# BEP33_2panel_v2_90Gradtvm802.net
KiCad netlist of a schematic drawn in EAGLE
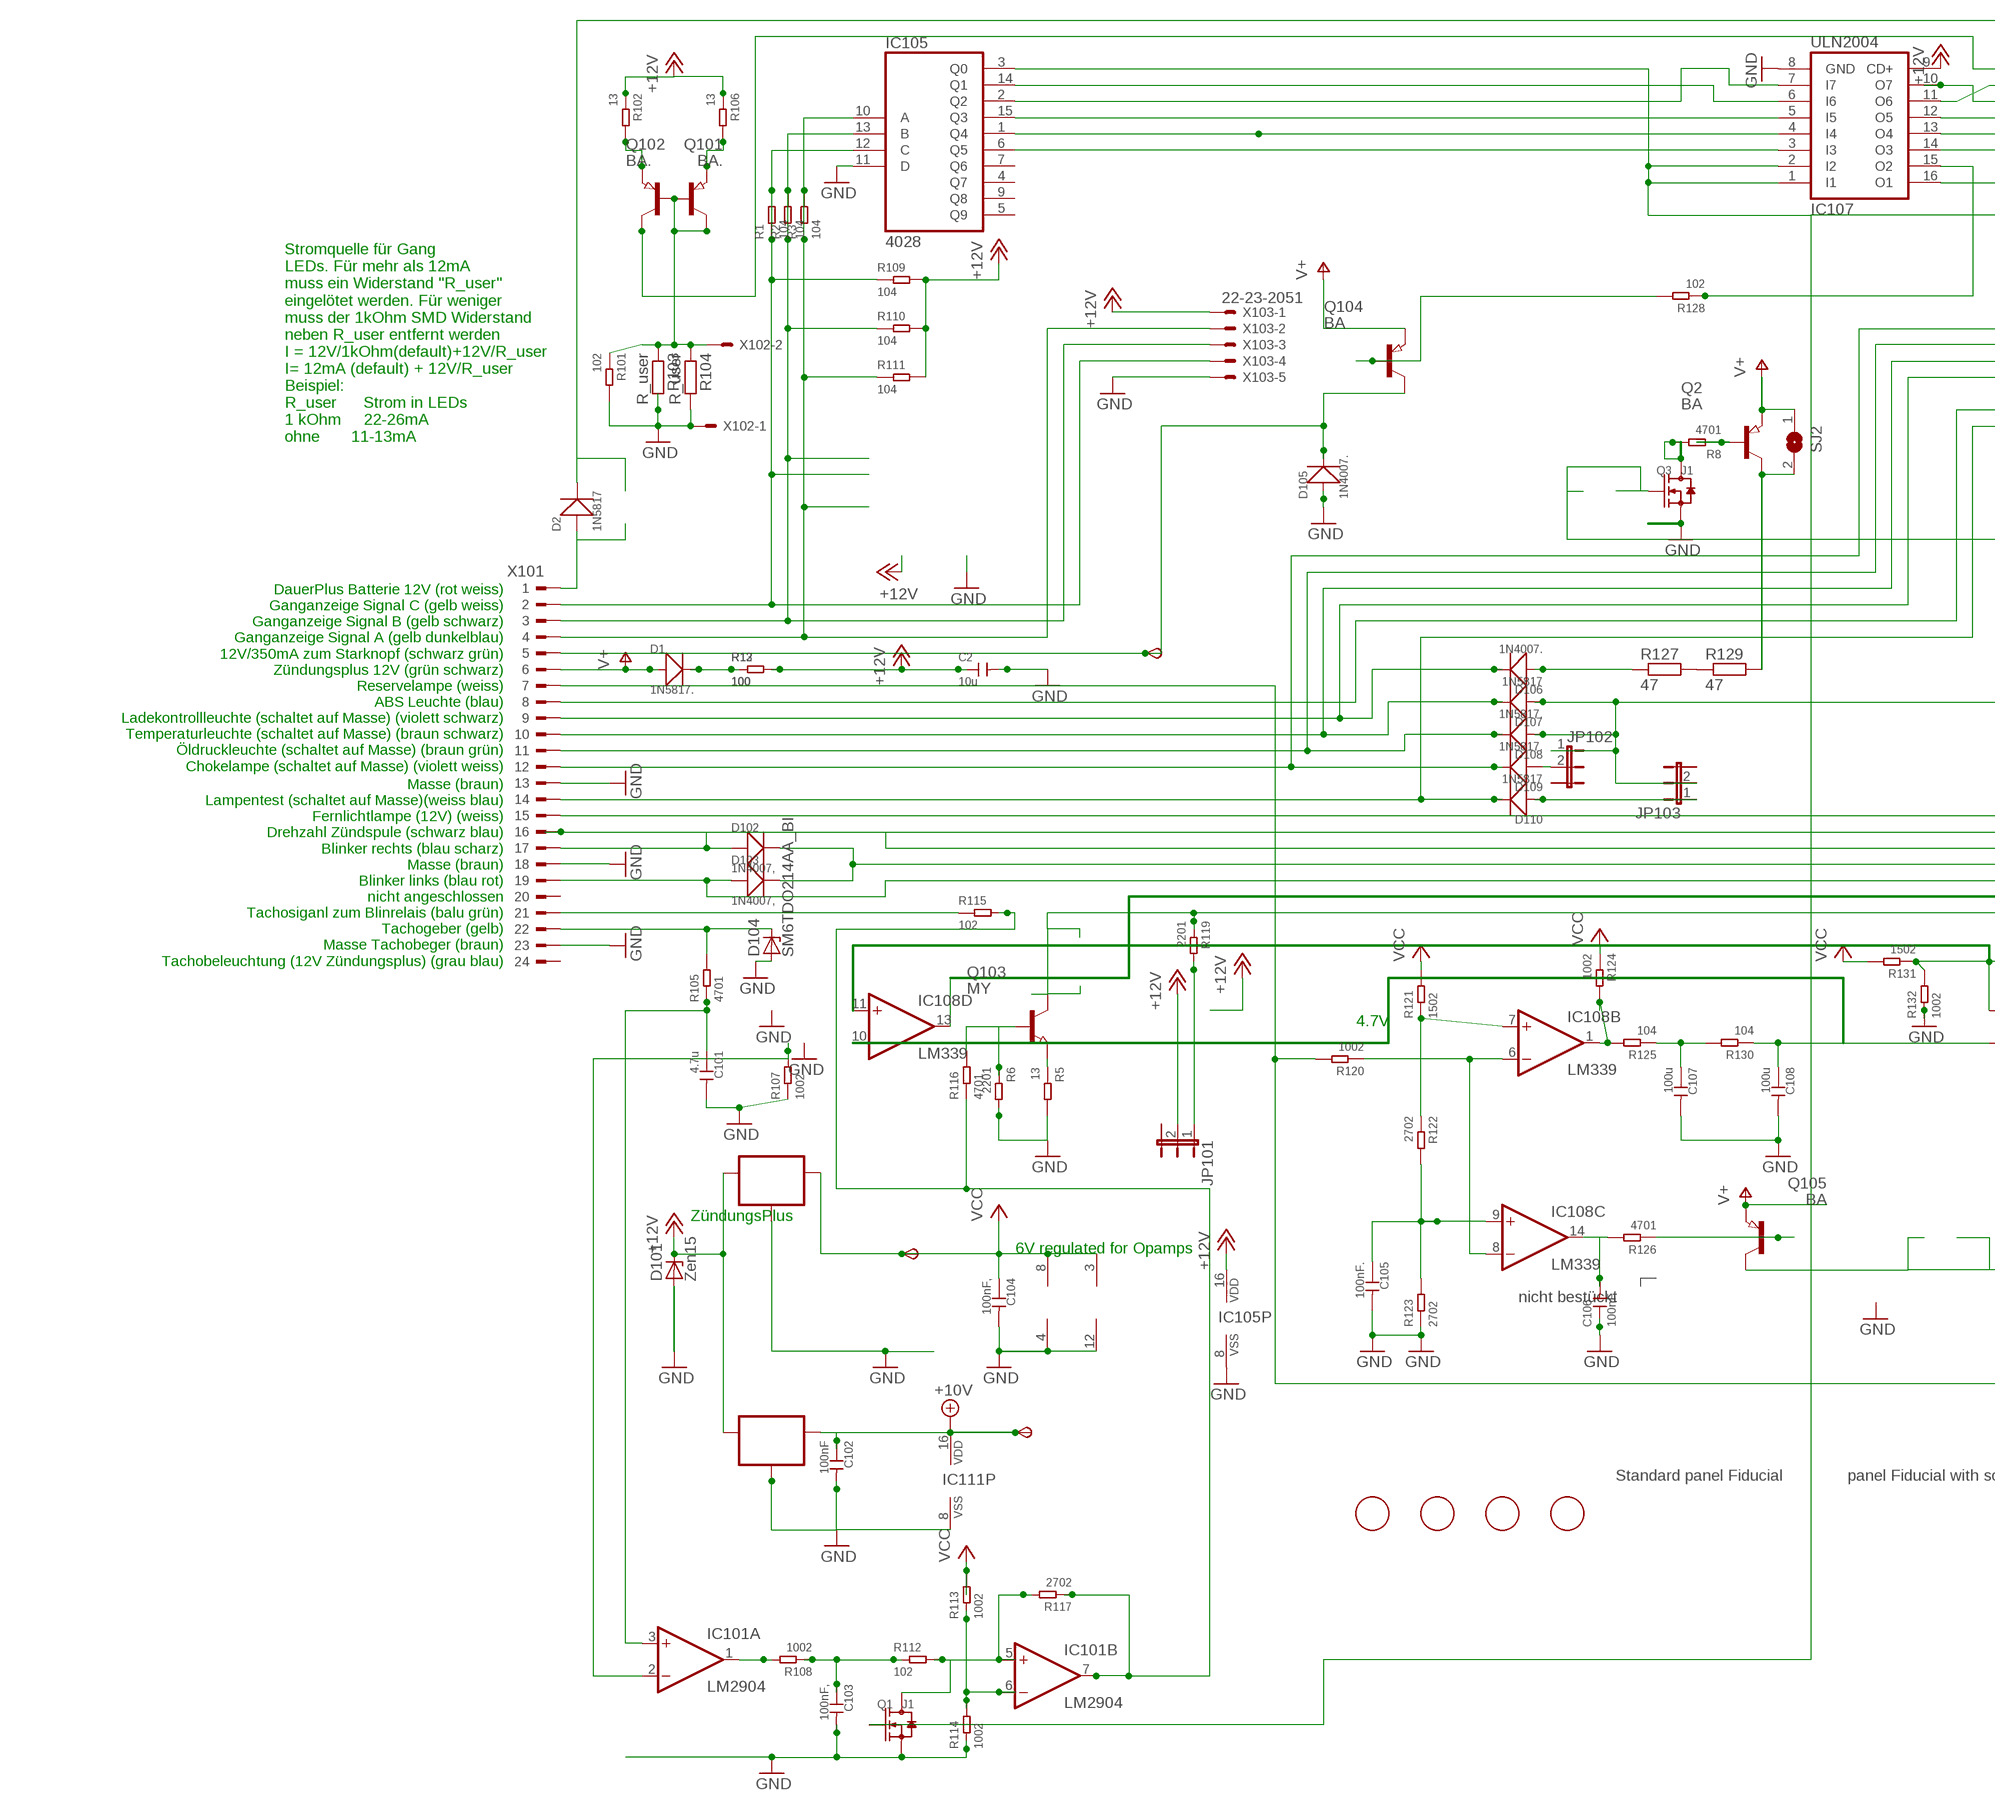
[diagram p0: schematic, sheet 1, part 1 of 2]
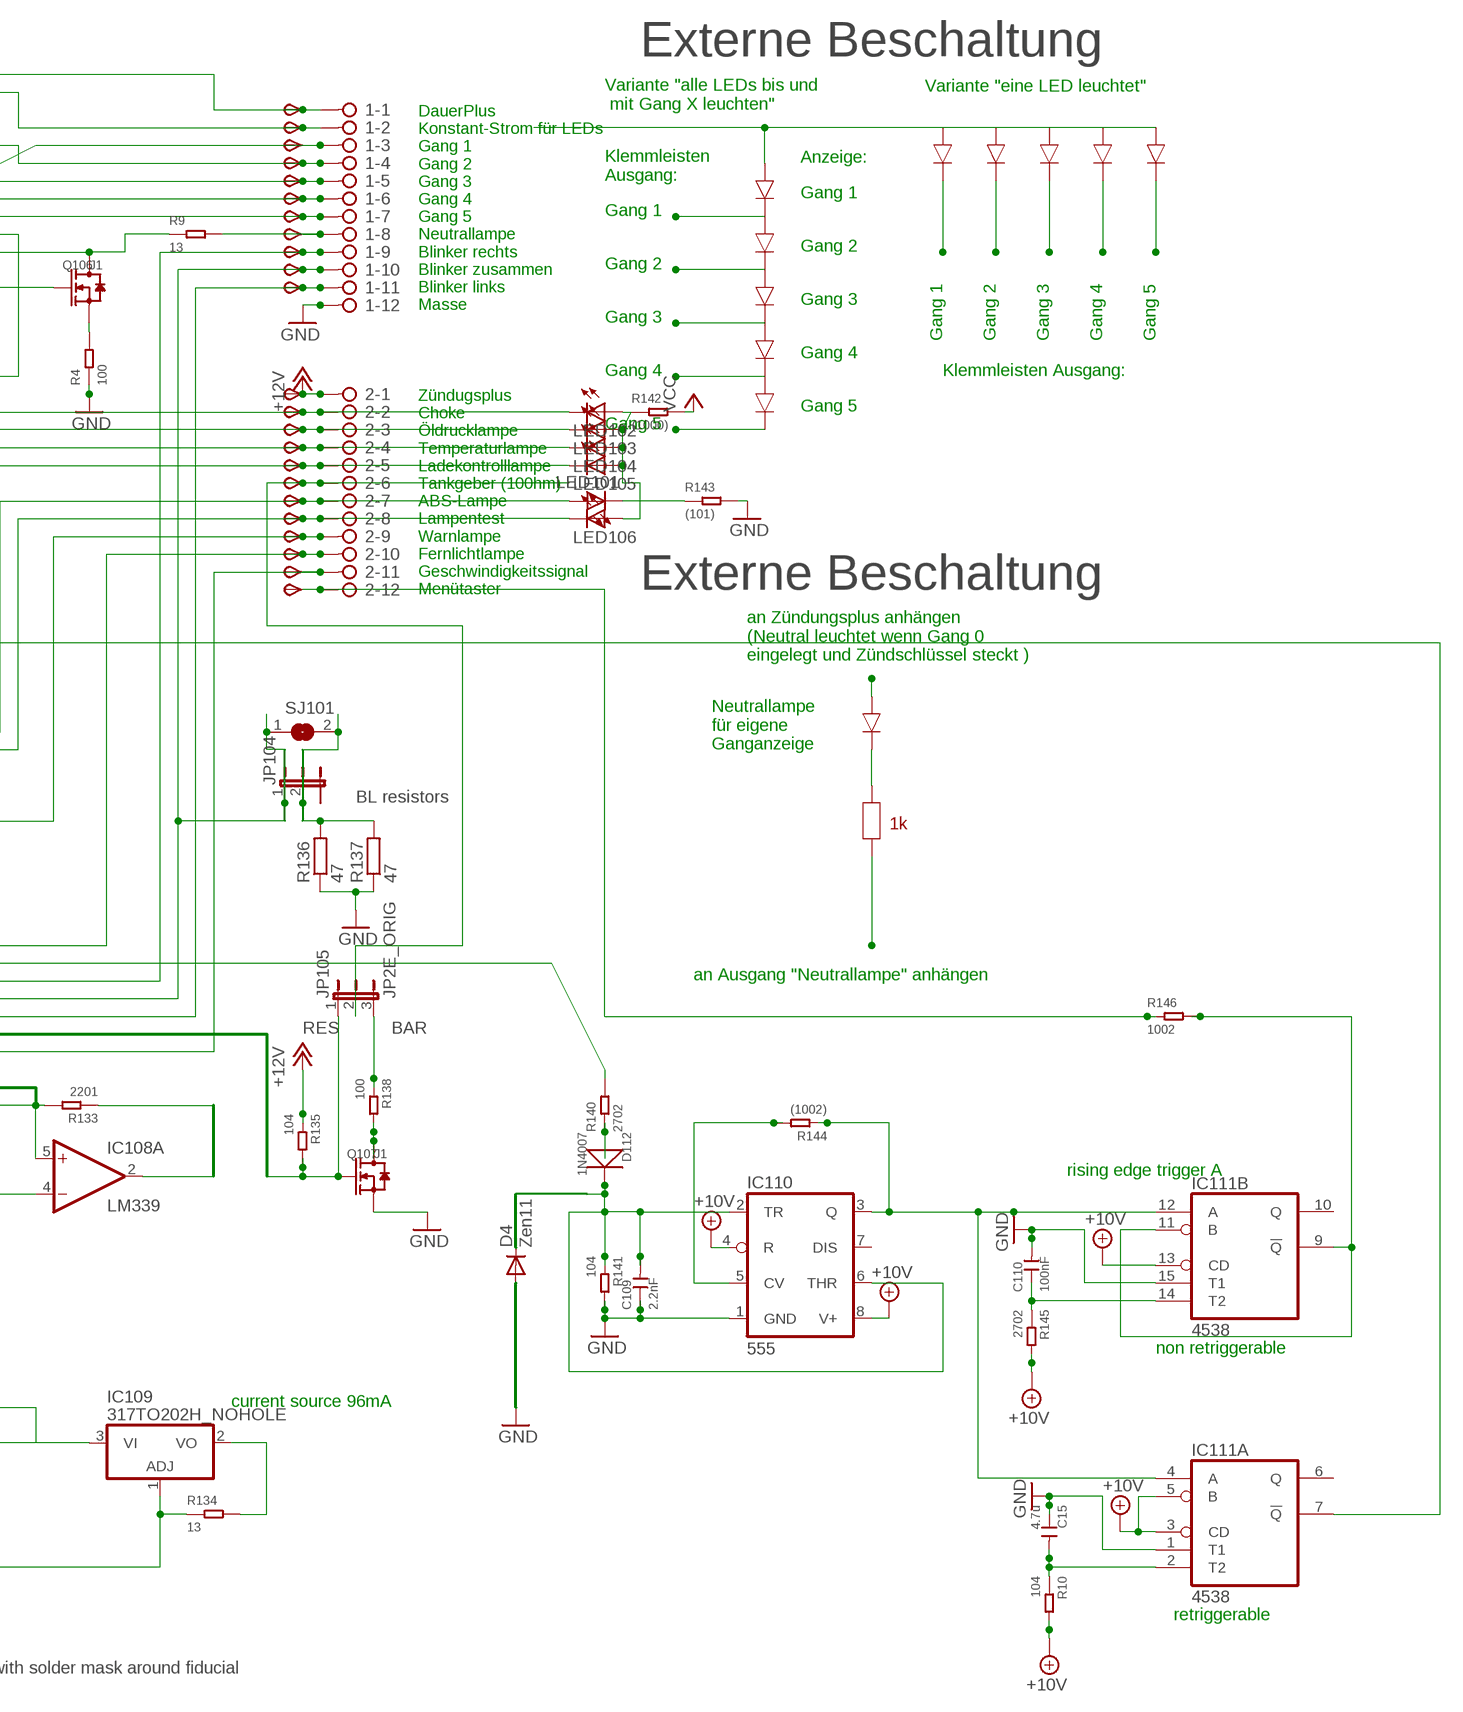
[diagram p1: schematic, sheet 1, part 2 of 2]

(export (version "E")
  (design (tool "Eeschema 10.0.6"))
  (components
    (comp (ref "1")
      (value "2081-1132")
      (footprint "eagle-import:12-PIN")
      (libsource (lib "eagle-import") (part "2081-1132"))
    )
    (comp (ref "2")
      (value "2081-1132")
      (footprint "eagle-import:12-PIN")
      (libsource (lib "eagle-import") (part "2081-1132"))
    )
    (comp (ref "6V")
      (value "TPSB2.0")
      (footprint "eagle-import:B2.0")
      (libsource (lib "eagle-import") (part "TPSB2.0"))
    )
    (comp (ref "10V")
      (value "TPSB2.0")
      (footprint "eagle-import:B2.0")
      (libsource (lib "eagle-import") (part "TPSB2.0"))
    )
    (comp (ref "C2")
      (value "10u")
      (footprint "eagle-import:C1206")
      (fields (field (name "MPN") "GRM31CR60J107ME39L"))
      (libsource (lib "eagle-import") (part "CERAMIC-100UF-6.3V-20%-X5R(1206)"))
    )
    (comp (ref "C15")
      (value "4.7u")
      (footprint "eagle-import:C0805")
      (fields (field (name "MPN") "CC0805KKX5R8BB475"))
      (libsource (lib "eagle-import") (part "CERAMIC-4.7UF-25V-10%-X5R(0805)"))
    )
    (comp (ref "C101")
      (value "4.7u")
      (footprint "eagle-import:C0805")
      (fields (field (name "MPN") "CC0805KKX5R8BB475"))
      (libsource (lib "eagle-import") (part "CERAMIC-4.7UF-25V-10%-X5R(0805)"))
    )
    (comp (ref "C102")
      (value "100nF")
      (footprint "eagle-import:C0805")
      (fields (field (name "MPN") "CC0805KRX7R9BB104"))
      (libsource (lib "eagle-import") (part "CERAMIC-100NF-50V-10%-X7R(0805)"))
    )
    (comp (ref "C103")
      (value "100nF,")
      (footprint "eagle-import:C0805")
      (fields (field (name "MPN") "CC0805KRX7R9BB104"))
      (libsource (lib "eagle-import") (part "CERAMIC-100NF-50V-10%-X7R(0805)"))
    )
    (comp (ref "C104")
      (value "100nF,")
      (footprint "eagle-import:C0805")
      (fields (field (name "MPN") "CC0805KRX7R9BB104"))
      (libsource (lib "eagle-import") (part "CERAMIC-100NF-50V-10%-X7R(0805)"))
    )
    (comp (ref "C105")
      (value "100nF.")
      (footprint "eagle-import:C0805")
      (fields (field (name "MPN") "CC0805KRX7R9BB104"))
      (libsource (lib "eagle-import") (part "CERAMIC-100NF-50V-10%-X7R(0805)"))
    )
    (comp (ref "C106")
      (value "100nF.")
      (footprint "eagle-import:C0805")
      (fields (field (name "MPN") "CC0805KRX7R9BB104"))
      (libsource (lib "eagle-import") (part "CERAMIC-100NF-50V-10%-X7R(0805)"))
    )
    (comp (ref "C107")
      (value "100u")
      (footprint "eagle-import:C1206")
      (fields (field (name "MPN") "GRM31CR60J107ME39L"))
      (libsource (lib "eagle-import") (part "CERAMIC-100UF-6.3V-20%-X5R(1206)"))
    )
    (comp (ref "C108")
      (value "100u")
      (footprint "eagle-import:C1206")
      (fields (field (name "MPN") "GRM31CR60J107ME39L"))
      (libsource (lib "eagle-import") (part "CERAMIC-100UF-6.3V-20%-X5R(1206)"))
    )
    (comp (ref "C109")
      (value "2.2nF")
      (footprint "eagle-import:C0805")
      (fields (field (name "MPN") "CC0805KRX7R9BB104"))
      (libsource (lib "eagle-import") (part "CERAMIC-100NF-50V-10%-X7R(0805)"))
    )
    (comp (ref "C110")
      (value "100nF")
      (footprint "eagle-import:C0805")
      (fields (field (name "MPN") "CC0805KRX7R9BB104"))
      (libsource (lib "eagle-import") (part "CERAMIC-100NF-50V-10%-X7R(0805)"))
    )
    (comp (ref "D1")
      (value "1N5817.")
      (footprint "eagle-import:DO-214AC_SLIM")
      (libsource (lib "eagle-import") (part "DIODE-GEN-PURPOSE-1KV-1A(DO-214AC)DO-214AC/1206"))
    )
    (comp (ref "D2")
      (value "1N5817")
      (footprint "eagle-import:DO-214AC_SLIM")
      (libsource (lib "eagle-import") (part "DIODE-GEN-PURPOSE-1KV-1A(DO-214AC)DO-214AC/1206"))
    )
    (comp (ref "D4")
      (value "Zen11")
      (footprint "eagle-import:SOD-123_MINI-SMA")
      (libsource (lib "eagle-import") (part "CGRM400-G1"))
    )
    (comp (ref "D101")
      (value "Zen15")
      (footprint "eagle-import:DO214AA")
      (libsource (lib "eagle-import") (part "SM6T"))
    )
    (comp (ref "D102")
      (value "1N4007,")
      (footprint "eagle-import:DO-214AC")
      (fields (field (name "MPN") "1N4007"))
      (libsource (lib "eagle-import") (part "DIODE-GEN-PURPOSE-1KV-1A(DO-214AC)"))
    )
    (comp (ref "D103")
      (value "1N4007,")
      (footprint "eagle-import:DO-214AC")
      (fields (field (name "MPN") "1N4007"))
      (libsource (lib "eagle-import") (part "DIODE-GEN-PURPOSE-1KV-1A(DO-214AC)"))
    )
    (comp (ref "D104")
      (value "SM6TDO214AA_BI")
      (footprint "eagle-import:DO214AA_BI")
      (libsource (lib "eagle-import") (part "SM6TDO214AA_BI"))
    )
    (comp (ref "D105")
      (value "1N4007.")
      (footprint "eagle-import:DO-214AC")
      (fields (field (name "MPN") "1N4007"))
      (libsource (lib "eagle-import") (part "DIODE-GEN-PURPOSE-1KV-1A(DO-214AC)"))
    )
    (comp (ref "D106")
      (value "1N4007.")
      (footprint "eagle-import:DO-214AC")
      (fields (field (name "MPN") "1N4007"))
      (libsource (lib "eagle-import") (part "DIODE-GEN-PURPOSE-1KV-1A(DO-214AC)"))
    )
    (comp (ref "D107")
      (value "1N5817")
      (footprint "eagle-import:DO-214AC_SLIM")
      (libsource (lib "eagle-import") (part "DIODE-GEN-PURPOSE-1KV-1A(DO-214AC)DO-214AC/1206"))
    )
    (comp (ref "D108")
      (value "1N5817.")
      (footprint "eagle-import:DO-214AC_SLIM")
      (libsource (lib "eagle-import") (part "DIODE-GEN-PURPOSE-1KV-1A(DO-214AC)DO-214AC/1206"))
    )
    (comp (ref "D109")
      (value "1N5817.")
      (footprint "eagle-import:DO-214AC_SLIM")
      (libsource (lib "eagle-import") (part "DIODE-GEN-PURPOSE-1KV-1A(DO-214AC)DO-214AC/1206"))
    )
    (comp (ref "D110")
      (value "1N5817")
      (footprint "eagle-import:DO-214AC_SLIM")
      (libsource (lib "eagle-import") (part "DIODE-GEN-PURPOSE-1KV-1A(DO-214AC)DO-214AC/1206"))
    )
    (comp (ref "D112")
      (value "1N4007")
      (footprint "eagle-import:DO-214AC")
      (libsource (lib "eagle-import") (part "DIODE-GEN-PURPOSE-1KV-1A(DO-214AC)"))
    )
    (comp (ref "FID1")
      (value "FIDUCIAL")
      (footprint "eagle-import:FIDUCIAL_1MM")
      (libsource (lib "eagle-import") (part "FIDUCIAL"))
    )
    (comp (ref "FID2")
      (value "FIDUCIAL")
      (footprint "eagle-import:FIDUCIAL_1MM")
      (libsource (lib "eagle-import") (part "FIDUCIAL"))
    )
    (comp (ref "FID102")
      (value "FIDUCIAL")
      (footprint "eagle-import:FIDUCIAL_1MM")
      (libsource (lib "eagle-import") (part "FIDUCIAL"))
    )
    (comp (ref "FID104")
      (value "FIDUCIAL")
      (footprint "eagle-import:FIDUCIAL_1MM")
      (libsource (lib "eagle-import") (part "FIDUCIAL"))
    )
    (comp (ref "IC101")
      (value "LM2904")
      (footprint "eagle-import:SO08")
      (libsource (lib "eagle-import") (part "LM358D"))
    )
    (comp (ref "IC102")
      (value "78L06")
      (footprint "eagle-import:SOT89_ROUND")
      (libsource (lib "eagle-import") (part "78LXXSOT89_ROUND"))
    )
    (comp (ref "IC104")
      (value "78L10")
      (footprint "eagle-import:SOT89_ROUND")
      (libsource (lib "eagle-import") (part "78LXXSOT89_ROUND"))
    )
    (comp (ref "IC105")
      (value "4028")
      (footprint "eagle-import:SO16")
      (libsource (lib "eagle-import") (part "4028D"))
    )
    (comp (ref "IC107")
      (value "ULN2004")
      (footprint "eagle-import:SO16")
      (libsource (lib "eagle-import") (part "ULN2004AD"))
    )
    (comp (ref "IC108")
      (value "LM339")
      (footprint "eagle-import:SO14")
      (libsource (lib "eagle-import") (part "LM339D"))
    )
    (comp (ref "IC109")
      (value "317TO202H_NOHOLE")
      (footprint "eagle-import:TO220H_NOHOLE")
      (libsource (lib "eagle-import") (part "317TO202H_NOHOLE"))
    )
    (comp (ref "IC110")
      (value "555")
      (footprint "eagle-import:SO08")
      (libsource (lib "eagle-import") (part "555DNE"))
    )
    (comp (ref "IC111")
      (value "4538")
      (footprint "eagle-import:SO16")
      (libsource (lib "eagle-import") (part "4538D"))
    )
    (comp (ref "JP101")
      (value "JP2EJP2_SMALLPADS")
      (footprint "eagle-import:JP2_SMALLPADS")
      (libsource (lib "eagle-import") (part "JP2EJP2_SMALLPADS"))
    )
    (comp (ref "JP102")
      (value "JP2EJP2_SMALLPADS")
      (footprint "eagle-import:JP2_SMALLPADS")
      (libsource (lib "eagle-import") (part "JP2EJP2_SMALLPADS"))
    )
    (comp (ref "JP103")
      (value "JP2EJP2_SMALLPADS")
      (footprint "eagle-import:JP2_SMALLPADS")
      (libsource (lib "eagle-import") (part "JP2EJP2_SMALLPADS"))
    )
    (comp (ref "JP104")
      (value "JP2EJP2_SMALLPADS")
      (footprint "eagle-import:JP2_SMALLPADS")
      (libsource (lib "eagle-import") (part "JP2EJP2_SMALLPADS"))
    )
    (comp (ref "JP105")
      (value "JP2E_ORIG")
      (footprint "eagle-import:JP2_ORIG_SMALLPADS")
      (libsource (lib "eagle-import") (part "JP2E_ORIG"))
    )
    (comp (ref "LED101")
      (value "LEDLD260")
      (footprint "eagle-import:LD260")
      (libsource (lib "eagle-import") (part "LEDLD260"))
    )
    (comp (ref "LED102")
      (value "LEDLD260")
      (footprint "eagle-import:LD260")
      (libsource (lib "eagle-import") (part "LEDLD260"))
    )
    (comp (ref "LED103")
      (value "LEDLD260")
      (footprint "eagle-import:LD260")
      (libsource (lib "eagle-import") (part "LEDLD260"))
    )
    (comp (ref "LED104")
      (value "LEDLD260")
      (footprint "eagle-import:LD260")
      (libsource (lib "eagle-import") (part "LEDLD260"))
    )
    (comp (ref "LED105")
      (value "LEDLD260")
      (footprint "eagle-import:LD260")
      (libsource (lib "eagle-import") (part "LEDLD260"))
    )
    (comp (ref "LED106")
      (value "LEDLD260")
      (footprint "eagle-import:LD260")
      (libsource (lib "eagle-import") (part "LEDLD260"))
    )
    (comp (ref "Q1")
      (value "J1")
      (footprint "eagle-import:SOT-23")
      (fields (field (name "MPN") "BSS138W-7-F"))
      (libsource (lib "eagle-import") (part "SMD-MOSFET-N-CH-50V-200MA-BSS138W-7-F(SOT-23)"))
    )
    (comp (ref "Q2")
      (value "BA")
      (footprint "eagle-import:SOT89")
      (libsource (lib "eagle-import") (part "PNP-TRANSISTOR_SOT89"))
    )
    (comp (ref "Q3")
      (value "J1")
      (footprint "eagle-import:SOT-23")
      (fields (field (name "MPN") "BSS138W-7-F"))
      (libsource (lib "eagle-import") (part "SMD-MOSFET-N-CH-50V-200MA-BSS138W-7-F(SOT-23)"))
    )
    (comp (ref "Q101")
      (value "BA.")
      (footprint "eagle-import:SOT89")
      (libsource (lib "eagle-import") (part "PNP-TRANSISTOR_SOT89"))
    )
    (comp (ref "Q102")
      (value "BA.")
      (footprint "eagle-import:SOT89")
      (libsource (lib "eagle-import") (part "PNP-TRANSISTOR_SOT89"))
    )
    (comp (ref "Q103")
      (value "MY")
      (footprint "eagle-import:SOT89")
      (libsource (lib "eagle-import") (part "NPN-TRANSISTOR_SOT89"))
    )
    (comp (ref "Q104")
      (value "BA")
      (footprint "eagle-import:SOT89")
      (libsource (lib "eagle-import") (part "PNP-TRANSISTOR_SOT89"))
    )
    (comp (ref "Q105")
      (value "BA")
      (footprint "eagle-import:SOT89")
      (libsource (lib "eagle-import") (part "PNP-TRANSISTOR_SOT89"))
    )
    (comp (ref "Q106")
      (value "J1")
      (footprint "eagle-import:SOT-23")
      (fields (field (name "MPN") "BSS138W-7-F"))
      (libsource (lib "eagle-import") (part "SMD-MOSFET-N-CH-50V-200MA-BSS138W-7-F(SOT-23)"))
    )
    (comp (ref "Q107")
      (value "J1")
      (footprint "eagle-import:SOT-23")
      (fields (field (name "MPN") "BSS138W-7-F"))
      (libsource (lib "eagle-import") (part "SMD-MOSFET-N-CH-50V-200MA-BSS138W-7-F(SOT-23)"))
    )
    (comp (ref "R1")
      (value "104")
      (footprint "eagle-import:R0805")
      (fields (field (name "MPN") "RC0805FR-0710KL"))
      (libsource (lib "eagle-import") (part "SMD-RES-10K-1%-1/8W(0805)"))
    )
    (comp (ref "R2")
      (value "104")
      (footprint "eagle-import:R0805")
      (fields (field (name "MPN") "RC0805FR-0710KL"))
      (libsource (lib "eagle-import") (part "SMD-RES-10K-1%-1/8W(0805)"))
    )
    (comp (ref "R3")
      (value "104")
      (footprint "eagle-import:R0805")
      (fields (field (name "MPN") "RC0805FR-0710KL"))
      (libsource (lib "eagle-import") (part "SMD-RES-10K-1%-1/8W(0805)"))
    )
    (comp (ref "R4")
      (value "100")
      (footprint "eagle-import:R0805")
      (fields (field (name "MPN") "RC0805JR-07220RL"))
      (libsource (lib "eagle-import") (part "SMD-RES-220R-5%-1/8W(0805)"))
    )
    (comp (ref "R5")
      (value "13")
      (footprint "eagle-import:R1206")
      (fields (field (name "MPN") "RC1206JR-0713RL"))
      (libsource (lib "eagle-import") (part "SMD-RES-13R-5%-1/4W(1206)"))
    )
    (comp (ref "R6")
      (value "2201")
      (footprint "eagle-import:R0805")
      (fields (field (name "MPN") "RC0805JR-071KL"))
      (libsource (lib "eagle-import") (part "SMD-RES-1K-5%-1/8W(0805)"))
    )
    (comp (ref "R8")
      (value "4701")
      (footprint "eagle-import:R0805")
      (fields (field (name "MPN") "RC0805JR-074K7L"))
      (libsource (lib "eagle-import") (part "SMD-RES-4.7K-5%-1/8W(0805)"))
    )
    (comp (ref "R9")
      (value "13")
      (footprint "eagle-import:R1206")
      (fields (field (name "MPN") "RC1206JR-0713RL"))
      (libsource (lib "eagle-import") (part "SMD-RES-13R-5%-1/4W(1206)"))
    )
    (comp (ref "R10")
      (value "104")
      (footprint "eagle-import:R0805")
      (fields (field (name "MPN") "RC0805JR-074K7L"))
      (libsource (lib "eagle-import") (part "SMD-RES-4.7K-5%-1/8W(0805)"))
    )
    (comp (ref "R12")
      (value "100")
      (footprint "eagle-import:R0805")
      (fields (field (name "MPN") "RC0805JR-072K2L"))
      (libsource (lib "eagle-import") (part "SMD-RES-2.2K-5%-1/8W(0805)"))
    )
    (comp (ref "R13")
      (value "100")
      (footprint "eagle-import:R0805")
      (fields (field (name "MPN") "RC0805JR-072K2L"))
      (libsource (lib "eagle-import") (part "SMD-RES-2.2K-5%-1/8W(0805)"))
    )
    (comp (ref "R101")
      (value "102")
      (footprint "eagle-import:R0805")
      (fields (field (name "MPN") "RC0805JR-071KL"))
      (libsource (lib "eagle-import") (part "SMD-RES-1K-5%-1/8W(0805)"))
    )
    (comp (ref "R102")
      (value "13")
      (footprint "eagle-import:R1206")
      (fields (field (name "MPN") "RC1206JR-0713RL"))
      (libsource (lib "eagle-import") (part "SMD-RES-13R-5%-1/4W(1206)"))
    )
    (comp (ref "R103")
      (value "R_user")
      (footprint "eagle-import:R0805")
      (libsource (lib "eagle-import") (part "R-EU_R0805"))
    )
    (comp (ref "R104")
      (value "R_user")
      (footprint "eagle-import:R0805")
      (libsource (lib "eagle-import") (part "R-EU_R0805"))
    )
    (comp (ref "R105")
      (value "4701")
      (footprint "eagle-import:R0805")
      (fields (field (name "MPN") "RC0805JR-074K7L"))
      (libsource (lib "eagle-import") (part "SMD-RES-4.7K-5%-1/8W(0805)"))
    )
    (comp (ref "R106")
      (value "13")
      (footprint "eagle-import:R1206")
      (fields (field (name "MPN") "RC1206JR-0713RL"))
      (libsource (lib "eagle-import") (part "SMD-RES-13R-5%-1/4W(1206)"))
    )
    (comp (ref "R107")
      (value "1002")
      (footprint "eagle-import:R0805")
      (fields (field (name "MPN") "RC0805FR-0710KL"))
      (libsource (lib "eagle-import") (part "SMD-RES-10K-1%-1/8W(0805)"))
    )
    (comp (ref "R108")
      (value "1002")
      (footprint "eagle-import:R0805")
      (fields (field (name "MPN") "RC0805FR-0710KL"))
      (libsource (lib "eagle-import") (part "SMD-RES-10K-1%-1/8W(0805)"))
    )
    (comp (ref "R109")
      (value "104")
      (footprint "eagle-import:R0805")
      (fields (field (name "MPN") "RC0805FR-0710KL"))
      (libsource (lib "eagle-import") (part "SMD-RES-10K-1%-1/8W(0805)"))
    )
    (comp (ref "R110")
      (value "104")
      (footprint "eagle-import:R0805")
      (fields (field (name "MPN") "RC0805FR-0710KL"))
      (libsource (lib "eagle-import") (part "SMD-RES-10K-1%-1/8W(0805)"))
    )
    (comp (ref "R111")
      (value "104")
      (footprint "eagle-import:R0805")
      (fields (field (name "MPN") "RC0805FR-0710KL"))
      (libsource (lib "eagle-import") (part "SMD-RES-10K-1%-1/8W(0805)"))
    )
    (comp (ref "R112")
      (value "102")
      (footprint "eagle-import:R0805")
      (fields (field (name "MPN") "RC0805JR-071KL"))
      (libsource (lib "eagle-import") (part "SMD-RES-1K-5%-1/8W(0805)"))
    )
    (comp (ref "R113")
      (value "1002")
      (footprint "eagle-import:R0805")
      (fields (field (name "MPN") "RC0805JR-071KL"))
      (libsource (lib "eagle-import") (part "SMD-RES-1K-5%-1/8W(0805)"))
    )
    (comp (ref "R114")
      (value "1002")
      (footprint "eagle-import:R0805")
      (fields (field (name "MPN") "RC0805JR-071KL"))
      (libsource (lib "eagle-import") (part "SMD-RES-1K-5%-1/8W(0805)"))
    )
    (comp (ref "R115")
      (value "102")
      (footprint "eagle-import:R0805")
      (fields (field (name "MPN") "RC0805JR-07220RL"))
      (libsource (lib "eagle-import") (part "SMD-RES-220R-5%-1/8W(0805)"))
    )
    (comp (ref "R116")
      (value "4701")
      (footprint "eagle-import:R0805")
      (fields (field (name "MPN") "RC0805JR-074K7L"))
      (libsource (lib "eagle-import") (part "SMD-RES-4.7K-5%-1/8W(0805)"))
    )
    (comp (ref "R117")
      (value "2702")
      (footprint "eagle-import:R0805")
      (fields (field (name "MPN") "RC0805JR-074K7L"))
      (libsource (lib "eagle-import") (part "SMD-RES-4.7K-5%-1/8W(0805)"))
    )
    (comp (ref "R119")
      (value "2201")
      (footprint "eagle-import:R0805")
      (fields (field (name "MPN") "RC0805JR-072K2L"))
      (libsource (lib "eagle-import") (part "SMD-RES-2.2K-5%-1/8W(0805)"))
    )
    (comp (ref "R120")
      (value "1002")
      (footprint "eagle-import:R0805")
      (fields (field (name "MPN") "RC0805FR-0710KL"))
      (libsource (lib "eagle-import") (part "SMD-RES-10K-1%-1/8W(0805)"))
    )
    (comp (ref "R121")
      (value "1502")
      (footprint "eagle-import:R0805")
      (fields (field (name "MPN") "RC0805FR-0710KL"))
      (libsource (lib "eagle-import") (part "SMD-RES-10K-1%-1/8W(0805)"))
    )
    (comp (ref "R122")
      (value "2702")
      (footprint "eagle-import:R0805")
      (fields (field (name "MPN") "RC0805JR-074K7L"))
      (libsource (lib "eagle-import") (part "SMD-RES-4.7K-5%-1/8W(0805)"))
    )
    (comp (ref "R123")
      (value "2702")
      (footprint "eagle-import:R0805")
      (fields (field (name "MPN") "RC0805JR-074K7L"))
      (libsource (lib "eagle-import") (part "SMD-RES-4.7K-5%-1/8W(0805)"))
    )
    (comp (ref "R124")
      (value "1002")
      (footprint "eagle-import:R0805")
      (fields (field (name "MPN") "RC0805FR-0710KL"))
      (libsource (lib "eagle-import") (part "SMD-RES-10K-1%-1/8W(0805)"))
    )
    (comp (ref "R125")
      (value "104")
      (footprint "eagle-import:R0805")
      (fields (field (name "MPN") "RC0805FR-0710KL"))
      (libsource (lib "eagle-import") (part "SMD-RES-10K-1%-1/8W(0805)"))
    )
    (comp (ref "R126")
      (value "4701")
      (footprint "eagle-import:R0805")
      (fields (field (name "MPN") "RC0805JR-074K7L"))
      (libsource (lib "eagle-import") (part "SMD-RES-4.7K-5%-1/8W(0805)"))
    )
    (comp (ref "R127")
      (value "47")
      (footprint "eagle-import:V235_17_1MM")
      (libsource (lib "eagle-import") (part "R-EU_V235/17_1MM"))
    )
    (comp (ref "R128")
      (value "102")
      (footprint "eagle-import:R0805")
      (fields (field (name "MPN") "RC0805JR-071KL"))
      (libsource (lib "eagle-import") (part "SMD-RES-1K-5%-1/8W(0805)"))
    )
    (comp (ref "R129")
      (value "47")
      (footprint "eagle-import:V235_17_1MM")
      (libsource (lib "eagle-import") (part "R-EU_V235/17_1MM"))
    )
    (comp (ref "R130")
      (value "104")
      (footprint "eagle-import:R0805")
      (fields (field (name "MPN") "RC0805FR-0710KL"))
      (libsource (lib "eagle-import") (part "SMD-RES-10K-1%-1/8W(0805)"))
    )
    (comp (ref "R131")
      (value "1502")
      (footprint "eagle-import:R0805")
      (fields (field (name "MPN") "RC0805FR-0710KL"))
      (libsource (lib "eagle-import") (part "SMD-RES-10K-1%-1/8W(0805)"))
    )
    (comp (ref "R132")
      (value "1002")
      (footprint "eagle-import:R0805")
      (fields (field (name "MPN") "RC0805FR-0710KL"))
      (libsource (lib "eagle-import") (part "SMD-RES-10K-1%-1/8W(0805)"))
    )
    (comp (ref "R133")
      (value "2201")
      (footprint "eagle-import:R0805")
      (fields (field (name "MPN") "RC0805JR-072K2L"))
      (libsource (lib "eagle-import") (part "SMD-RES-2.2K-5%-1/8W(0805)"))
    )
    (comp (ref "R134")
      (value "13")
      (footprint "eagle-import:R1206")
      (fields (field (name "MPN") "RC1206JR-0713RL"))
      (libsource (lib "eagle-import") (part "SMD-RES-13R-5%-1/4W(1206)"))
    )
    (comp (ref "R135")
      (value "104")
      (footprint "eagle-import:R0805")
      (fields (field (name "MPN") "RC0805FR-0710KL"))
      (libsource (lib "eagle-import") (part "SMD-RES-10K-1%-1/8W(0805)"))
    )
    (comp (ref "R136")
      (value "47")
      (footprint "eagle-import:V235_17_1MM")
      (libsource (lib "eagle-import") (part "R-EU_V235/17_1MM"))
    )
    (comp (ref "R137")
      (value "47")
      (footprint "eagle-import:V235_17_1MM")
      (libsource (lib "eagle-import") (part "R-EU_V235/17_1MM"))
    )
    (comp (ref "R138")
      (value "100")
      (footprint "eagle-import:R0805")
      (fields (field (name "MPN") "RC0805JR-072K2L"))
      (libsource (lib "eagle-import") (part "SMD-RES-2.2K-5%-1/8W(0805)"))
    )
    (comp (ref "R140")
      (value "2702")
      (footprint "eagle-import:R0805")
      (fields (field (name "MPN") "RC0805FR-0710KL"))
      (libsource (lib "eagle-import") (part "SMD-RES-10K-1%-1/8W(0805)"))
    )
    (comp (ref "R141")
      (value "104")
      (footprint "eagle-import:R0805")
      (fields (field (name "MPN") "RC0805FR-0710KL"))
      (libsource (lib "eagle-import") (part "SMD-RES-10K-1%-1/8W(0805)"))
    )
    (comp (ref "R142")
      (value "(1000)")
      (footprint "eagle-import:R0805")
      (fields (field (name "MPN") "RC0805JR-07100RL"))
      (libsource (lib "eagle-import") (part "SMD-RES-100R-5%-1/8W(0805)"))
    )
    (comp (ref "R143")
      (value "(101)")
      (footprint "eagle-import:R0805")
      (fields (field (name "MPN") "RC0805JR-07100RL"))
      (libsource (lib "eagle-import") (part "SMD-RES-100R-5%-1/8W(0805)"))
    )
    (comp (ref "R144")
      (value "(1002)")
      (footprint "eagle-import:R0805")
      (fields (field (name "MPN") "RC0805FR-0710KL"))
      (libsource (lib "eagle-import") (part "SMD-RES-10K-1%-1/8W(0805)"))
    )
    (comp (ref "R145")
      (value "2702")
      (footprint "eagle-import:R0805")
      (fields (field (name "MPN") "RC0805JR-074K7L"))
      (libsource (lib "eagle-import") (part "SMD-RES-4.7K-5%-1/8W(0805)"))
    )
    (comp (ref "R146")
      (value "1002")
      (footprint "eagle-import:R0805")
      (fields (field (name "MPN") "RC0805JR-074K7L"))
      (libsource (lib "eagle-import") (part "SMD-RES-4.7K-5%-1/8W(0805)"))
    )
    (comp (ref "SJ2") (value "SJ") (footprint "eagle-import:SJ") (libsource (lib "eagle-import") (part "SJ")))
    (comp (ref "SJ101")
      (value "SJ")
      (footprint "eagle-import:SJ")
      (libsource (lib "eagle-import") (part "solder-jumper_SJ"))
    )
    (comp (ref "START")
      (value "TPSB2.0")
      (footprint "eagle-import:B2.0")
      (libsource (lib "eagle-import") (part "TPSB2.0"))
    )
    (comp (ref "TP1")
      (value "TPSB2.0")
      (footprint "eagle-import:B2.0")
      (libsource (lib "eagle-import") (part "TPSB2.0"))
    )
    (comp (ref "TP2")
      (value "TPSB2.0")
      (footprint "eagle-import:B2.0")
      (libsource (lib "eagle-import") (part "TPSB2.0"))
    )
    (comp (ref "TP3")
      (value "TPSB2.0")
      (footprint "eagle-import:B2.0")
      (libsource (lib "eagle-import") (part "TPSB2.0"))
    )
    (comp (ref "TP4")
      (value "TPSB2.0")
      (footprint "eagle-import:B2.0")
      (libsource (lib "eagle-import") (part "TPSB2.0"))
    )
    (comp (ref "TP5")
      (value "TPSB2.0")
      (footprint "eagle-import:B2.0")
      (libsource (lib "eagle-import") (part "TPSB2.0"))
    )
    (comp (ref "TP6")
      (value "TPSB2.0")
      (footprint "eagle-import:B2.0")
      (libsource (lib "eagle-import") (part "TPSB2.0"))
    )
    (comp (ref "TP7")
      (value "TPSB2.0")
      (footprint "eagle-import:B2.0")
      (libsource (lib "eagle-import") (part "TPSB2.0"))
    )
    (comp (ref "TP8")
      (value "TPSB2.0")
      (footprint "eagle-import:B2.0")
      (libsource (lib "eagle-import") (part "TPSB2.0"))
    )
    (comp (ref "TP9")
      (value "TPSB2.0")
      (footprint "eagle-import:B2.0")
      (libsource (lib "eagle-import") (part "TPSB2.0"))
    )
    (comp (ref "TP10")
      (value "TPSB2.0")
      (footprint "eagle-import:B2.0")
      (libsource (lib "eagle-import") (part "TPSB2.0"))
    )
    (comp (ref "TP11")
      (value "TPSB2.0")
      (footprint "eagle-import:B2.0")
      (libsource (lib "eagle-import") (part "TPSB2.0"))
    )
    (comp (ref "TP12")
      (value "TPSB2.0")
      (footprint "eagle-import:B2.0")
      (libsource (lib "eagle-import") (part "TPSB2.0"))
    )
    (comp (ref "TP13")
      (value "TPSB2.0")
      (footprint "eagle-import:B2.0")
      (libsource (lib "eagle-import") (part "TPSB2.0"))
    )
    (comp (ref "TP16")
      (value "TPSB2.0")
      (footprint "eagle-import:B2.0")
      (libsource (lib "eagle-import") (part "TPSB2.0"))
    )
    (comp (ref "TP17")
      (value "TPSB2.0")
      (footprint "eagle-import:B2.0")
      (libsource (lib "eagle-import") (part "TPSB2.0"))
    )
    (comp (ref "TP18")
      (value "TPSB2.0")
      (footprint "eagle-import:B2.0")
      (libsource (lib "eagle-import") (part "TPSB2.0"))
    )
    (comp (ref "TP19")
      (value "TPSB2.0")
      (footprint "eagle-import:B2.0")
      (libsource (lib "eagle-import") (part "TPSB2.0"))
    )
    (comp (ref "TP21")
      (value "TPSB2.0")
      (footprint "eagle-import:B2.0")
      (libsource (lib "eagle-import") (part "TPSB2.0"))
    )
    (comp (ref "TP22")
      (value "TPSB2.0")
      (footprint "eagle-import:B2.0")
      (libsource (lib "eagle-import") (part "TPSB2.0"))
    )
    (comp (ref "TP23")
      (value "TPSB2.0")
      (footprint "eagle-import:B2.0")
      (libsource (lib "eagle-import") (part "TPSB2.0"))
    )
    (comp (ref "TP24")
      (value "TPSB1,27")
      (footprint "eagle-import:B1,27")
      (libsource (lib "eagle-import") (part "TPSB1,27"))
    )
    (comp (ref "TP25")
      (value "TPSB2.0")
      (footprint "eagle-import:B2.0")
      (libsource (lib "eagle-import") (part "TPSB2.0"))
    )
    (comp (ref "TP26")
      (value "TPSB2.0")
      (footprint "eagle-import:B2.0")
      (libsource (lib "eagle-import") (part "TPSB2.0"))
    )
    (comp (ref "X101")
      (value "CON_BMWV2")
      (footprint "eagle-import:24-PIN_V2")
      (libsource (lib "eagle-import") (part "CON_BMWV2"))
    )
    (comp (ref "X102")
      (value "22-23-2021")
      (footprint "eagle-import:22-23-2021")
      (fields (field (name "MF") "MOLEX"))
      (libsource (lib "eagle-import") (part "22-23-2021"))
    )
    (comp (ref "X103")
      (value "22-23-2051")
      (footprint "eagle-import:22-23-2051")
      (fields (field (name "MF") "MOLEX"))
      (libsource (lib "eagle-import") (part "22-23-2051"))
    )
  )
  (nets
    (net (code "1") (name "+10V") (class "Default")
      (node (ref "10V") (pin "TP") (pinfunction "PP_TP") (pintype "input"))
      (node (ref "C102") (pin "1") (pinfunction "1_1") (pintype "passive"))
      (node (ref "IC104") (pin "1") (pinfunction "OUT_1") (pintype "passive"))
      (node (ref "IC110") (pin "4") (pinfunction "R_4") (pintype "input"))
      (node (ref "IC110") (pin "8") (pinfunction "V+_8") (pintype "power_in"))
      (node (ref "IC111") (pin "13") (pinfunction "CD_13") (pintype "input"))
      (node (ref "IC111") (pin "16") (pinfunction "VDD_16") (pintype "power_in"))
      (node (ref "IC111") (pin "3") (pinfunction "CD_3") (pintype "input"))
      (node (ref "IC111") (pin "5") (pinfunction "B_5") (pintype "input"))
      (node (ref "R10") (pin "2") (pinfunction "2_2") (pintype "passive"))
      (node (ref "R145") (pin "2") (pinfunction "2_2") (pintype "passive"))
    )
    (net (code "2") (name "+12V") (class "Default")
      (node (ref "2") (pin "1") (pinfunction "KL_1") (pintype "passive"))
      (node (ref "C2") (pin "1") (pinfunction "1_1") (pintype "passive"))
      (node (ref "D101") (pin "C") (pinfunction "C_C") (pintype "passive"))
      (node (ref "IC102") (pin "3") (pinfunction "IN_3") (pintype "input"))
      (node (ref "IC104") (pin "3") (pinfunction "IN_3") (pintype "input"))
      (node (ref "IC105") (pin "16") (pinfunction "VDD_16") (pintype "power_in"))
      (node (ref "IC107") (pin "9") (pinfunction "CD+_9") (pintype "passive"))
      (node (ref "JP101") (pin "2") (pinfunction "2_2") (pintype "passive"))
      (node (ref "R102") (pin "1") (pinfunction "1_1") (pintype "passive"))
      (node (ref "R106") (pin "1") (pinfunction "1_1") (pintype "passive"))
      (node (ref "R109") (pin "2") (pinfunction "2_2") (pintype "passive"))
      (node (ref "R110") (pin "2") (pinfunction "2_2") (pintype "passive"))
      (node (ref "R111") (pin "2") (pinfunction "2_2") (pintype "passive"))
      (node (ref "R12") (pin "2") (pinfunction "2_2") (pintype "passive"))
      (node (ref "R13") (pin "2") (pinfunction "2_2") (pintype "passive"))
      (node (ref "R135") (pin "1") (pinfunction "1_1") (pintype "passive"))
      (node (ref "TP12") (pin "TP") (pinfunction "PP_TP") (pintype "input"))
      (node (ref "X103") (pin "1") (pinfunction "S_1") (pintype "passive"))
    )
    (net (code "3") (name "GND") (class "Default")
      (node (ref "1") (pin "12") (pinfunction "KL_12") (pintype "passive"))
      (node (ref "C101") (pin "2") (pinfunction "2_2") (pintype "passive"))
      (node (ref "C102") (pin "2") (pinfunction "2_2") (pintype "passive"))
      (node (ref "C103") (pin "2") (pinfunction "2_2") (pintype "passive"))
      (node (ref "C104") (pin "2") (pinfunction "2_2") (pintype "passive"))
      (node (ref "C105") (pin "2") (pinfunction "2_2") (pintype "passive"))
      (node (ref "C106") (pin "1") (pinfunction "1_1") (pintype "passive"))
      (node (ref "C107") (pin "2") (pinfunction "2_2") (pintype "passive"))
      (node (ref "C108") (pin "2") (pinfunction "2_2") (pintype "passive"))
      (node (ref "C109") (pin "1") (pinfunction "1_1") (pintype "passive"))
      (node (ref "C110") (pin "2") (pinfunction "2_2") (pintype "passive"))
      (node (ref "C15") (pin "1") (pinfunction "1_1") (pintype "passive"))
      (node (ref "C2") (pin "2") (pinfunction "2_2") (pintype "passive"))
      (node (ref "D101") (pin "A") (pinfunction "A_A") (pintype "passive"))
      (node (ref "D104") (pin "A") (pinfunction "A_A") (pintype "passive"))
      (node (ref "D105") (pin "1") (pinfunction "+_1") (pintype "passive"))
      (node (ref "D4") (pin "A") (pinfunction "A_A") (pintype "passive"))
      (node (ref "IC101") (pin "4") (pinfunction "V-_4") (pintype "power_in"))
      (node (ref "IC102") (pin "2") (pinfunction "GND_2") (pintype "input"))
      (node (ref "IC102") (pin "2@1") (pinfunction "GND_2@1") (pintype "input"))
      (node (ref "IC104") (pin "2") (pinfunction "GND_2") (pintype "input"))
      (node (ref "IC104") (pin "2@1") (pinfunction "GND_2@1") (pintype "input"))
      (node (ref "IC105") (pin "11") (pinfunction "D_11") (pintype "input"))
      (node (ref "IC105") (pin "8") (pinfunction "VSS_8") (pintype "power_in"))
      (node (ref "IC107") (pin "8") (pinfunction "GND_8") (pintype "power_in"))
      (node (ref "IC108") (pin "12") (pinfunction "GND_12") (pintype "power_in"))
      (node (ref "IC110") (pin "1") (pinfunction "GND_1") (pintype "power_in"))
      (node (ref "IC111") (pin "1") (pinfunction "T1_1") (pintype "input"))
      (node (ref "IC111") (pin "15") (pinfunction "T1_15") (pintype "input"))
      (node (ref "IC111") (pin "8") (pinfunction "VSS_8") (pintype "power_in"))
      (node (ref "Q1") (pin "2") (pinfunction "S_2") (pintype "passive"))
      (node (ref "Q107") (pin "2") (pinfunction "S_2") (pintype "passive"))
      (node (ref "Q3") (pin "2") (pinfunction "S_2") (pintype "passive"))
      (node (ref "R101") (pin "2") (pinfunction "2_2") (pintype "passive"))
      (node (ref "R103") (pin "2") (pinfunction "2_2") (pintype "passive"))
      (node (ref "R104") (pin "2") (pinfunction "2_2") (pintype "passive"))
      (node (ref "R107") (pin "1") (pinfunction "1_1") (pintype "passive"))
      (node (ref "R114") (pin "1") (pinfunction "1_1") (pintype "passive"))
      (node (ref "R123") (pin "1") (pinfunction "1_1") (pintype "passive"))
      (node (ref "R132") (pin "1") (pinfunction "1_1") (pintype "passive"))
      (node (ref "R136") (pin "1") (pinfunction "1_1") (pintype "passive"))
      (node (ref "R137") (pin "1") (pinfunction "1_1") (pintype "passive"))
      (node (ref "R141") (pin "2") (pinfunction "2_2") (pintype "passive"))
      (node (ref "R143") (pin "2") (pinfunction "2_2") (pintype "passive"))
      (node (ref "R4") (pin "1") (pinfunction "1_1") (pintype "passive"))
      (node (ref "R5") (pin "2") (pinfunction "2_2") (pintype "passive"))
      (node (ref "R6") (pin "2") (pinfunction "2_2") (pintype "passive"))
      (node (ref "X101") (pin "13") (pinfunction "13_13") (pintype "passive"))
      (node (ref "X101") (pin "18") (pinfunction "18_18") (pintype "passive"))
      (node (ref "X101") (pin "23") (pinfunction "23_23") (pintype "passive"))
      (node (ref "X102") (pin "1") (pinfunction "S_1") (pintype "passive"))
      (node (ref "X103") (pin "5") (pinfunction "S_5") (pintype "passive"))
    )
    (net (code "4") (name "Net-(1A-KL)") (class "Default")
      (node (ref "1") (pin "1") (pinfunction "KL_1") (pintype "passive"))
      (node (ref "D2") (pin "2") (pinfunction "-_2") (pintype "passive"))
      (node (ref "TP1") (pin "TP") (pinfunction "PP_TP") (pintype "input"))
    )
    (net (code "5") (name "Net-(1B-KL)") (class "Default")
      (node (ref "1") (pin "10") (pinfunction "KL_10") (pintype "passive"))
      (node (ref "D102") (pin "2") (pinfunction "-_2") (pintype "passive"))
      (node (ref "D103") (pin "2") (pinfunction "-_2") (pintype "passive"))
      (node (ref "JP104") (pin "1") (pinfunction "1_1") (pintype "passive"))
      (node (ref "SJ101") (pin "1") (pinfunction "1_1") (pintype "passive"))
      (node (ref "TP10") (pin "TP") (pinfunction "PP_TP") (pintype "input"))
    )
    (net (code "6") (name "Net-(1C-KL)") (class "Default")
      (node (ref "1") (pin "11") (pinfunction "KL_11") (pintype "passive"))
      (node (ref "D103") (pin "1") (pinfunction "+_1") (pintype "passive"))
      (node (ref "TP11") (pin "TP") (pinfunction "PP_TP") (pintype "input"))
      (node (ref "X101") (pin "19") (pinfunction "19_19") (pintype "passive"))
    )
    (net (code "7") (name "Net-(1E-KL)") (class "Default")
      (node (ref "1") (pin "2") (pinfunction "KL_2") (pintype "passive"))
      (node (ref "Q101") (pin "2") (pinfunction "C_2") (pintype "passive"))
      (node (ref "TP2") (pin "TP") (pinfunction "PP_TP") (pintype "input"))
    )
    (net (code "8") (name "Net-(1F-KL)") (class "Default")
      (node (ref "1") (pin "3") (pinfunction "KL_3") (pintype "passive"))
      (node (ref "IC107") (pin "11") (pinfunction "O6_11") (pintype "open_collector"))
      (node (ref "TP3") (pin "TP") (pinfunction "PP_TP") (pintype "input"))
    )
    (net (code "9") (name "Net-(1G-KL)") (class "Default")
      (node (ref "1") (pin "4") (pinfunction "KL_4") (pintype "passive"))
      (node (ref "IC107") (pin "10") (pinfunction "O7_10") (pintype "open_collector"))
      (node (ref "TP4") (pin "TP") (pinfunction "PP_TP") (pintype "input"))
    )
    (net (code "10") (name "Net-(1H-KL)") (class "Default")
      (node (ref "1") (pin "5") (pinfunction "KL_5") (pintype "passive"))
      (node (ref "IC107") (pin "12") (pinfunction "O5_12") (pintype "open_collector"))
      (node (ref "TP5") (pin "TP") (pinfunction "PP_TP") (pintype "input"))
    )
    (net (code "11") (name "Net-(1I-KL)") (class "Default")
      (node (ref "1") (pin "6") (pinfunction "KL_6") (pintype "passive"))
      (node (ref "IC107") (pin "13") (pinfunction "O4_13") (pintype "open_collector"))
      (node (ref "TP6") (pin "TP") (pinfunction "PP_TP") (pintype "input"))
    )
    (net (code "12") (name "Net-(1J-KL)") (class "Default")
      (node (ref "1") (pin "7") (pinfunction "KL_7") (pintype "passive"))
      (node (ref "IC107") (pin "14") (pinfunction "O3_14") (pintype "open_collector"))
      (node (ref "TP7") (pin "TP") (pinfunction "PP_TP") (pintype "input"))
    )
    (net (code "13") (name "Net-(1K-KL)") (class "Default")
      (node (ref "1") (pin "8") (pinfunction "KL_8") (pintype "passive"))
      (node (ref "R9") (pin "2") (pinfunction "2_2") (pintype "passive"))
      (node (ref "TP8") (pin "TP") (pinfunction "PP_TP") (pintype "input"))
    )
    (net (code "14") (name "Net-(1L-KL)") (class "Default")
      (node (ref "1") (pin "9") (pinfunction "KL_9") (pintype "passive"))
      (node (ref "D102") (pin "1") (pinfunction "+_1") (pintype "passive"))
      (node (ref "TP9") (pin "TP") (pinfunction "PP_TP") (pintype "input"))
      (node (ref "X101") (pin "17") (pinfunction "17_17") (pintype "passive"))
    )
    (net (code "15") (name "Net-(2B-KL)") (class "Default")
      (node (ref "2") (pin "10") (pinfunction "KL_10") (pintype "passive"))
      (node (ref "TP25") (pin "TP") (pinfunction "PP_TP") (pintype "input"))
      (node (ref "X101") (pin "15") (pinfunction "15_15") (pintype "passive"))
    )
    (net (code "16") (name "Net-(2C-KL)") (class "Default")
      (node (ref "2") (pin "11") (pinfunction "KL_11") (pintype "passive"))
      (node (ref "Q103") (pin "2") (pinfunction "C_2") (pintype "passive"))
      (node (ref "R119") (pin "1") (pinfunction "1_1") (pintype "passive"))
      (node (ref "TP26") (pin "TP") (pinfunction "PP_TP") (pintype "input"))
    )
    (net (code "17") (name "Net-(2D-KL)") (class "Default")
      (node (ref "2") (pin "12") (pinfunction "KL_12") (pintype "passive"))
      (node (ref "R146") (pin "1") (pinfunction "1_1") (pintype "passive"))
      (node (ref "TP13") (pin "TP") (pinfunction "PP_TP") (pintype "input"))
    )
    (net (code "18") (name "Net-(2E-KL)") (class "Default")
      (node (ref "2") (pin "2") (pinfunction "KL_2") (pintype "passive"))
      (node (ref "D109") (pin "2") (pinfunction "-_2") (pintype "passive"))
      (node (ref "LED102") (pin "K") (pinfunction "C_K") (pintype "passive"))
      (node (ref "TP16") (pin "TP") (pinfunction "PP_TP") (pintype "input"))
      (node (ref "X101") (pin "12") (pinfunction "12_12") (pintype "passive"))
    )
    (net (code "19") (name "Net-(2F-KL)") (class "Default")
      (node (ref "2") (pin "3") (pinfunction "KL_3") (pintype "passive"))
      (node (ref "D108") (pin "2") (pinfunction "-_2") (pintype "passive"))
      (node (ref "LED103") (pin "K") (pinfunction "C_K") (pintype "passive"))
      (node (ref "TP17") (pin "TP") (pinfunction "PP_TP") (pintype "input"))
      (node (ref "X101") (pin "11") (pinfunction "11_11") (pintype "passive"))
    )
    (net (code "20") (name "Net-(2G-KL)") (class "Default")
      (node (ref "2") (pin "4") (pinfunction "KL_4") (pintype "passive"))
      (node (ref "D107") (pin "2") (pinfunction "-_2") (pintype "passive"))
      (node (ref "LED104") (pin "K") (pinfunction "C_K") (pintype "passive"))
      (node (ref "TP18") (pin "TP") (pinfunction "PP_TP") (pintype "input"))
      (node (ref "X101") (pin "10") (pinfunction "10_10") (pintype "passive"))
    )
    (net (code "21") (name "Net-(2H-KL)") (class "Default")
      (node (ref "2") (pin "5") (pinfunction "KL_5") (pintype "passive"))
      (node (ref "D106") (pin "2") (pinfunction "-_2") (pintype "passive"))
      (node (ref "LED105") (pin "K") (pinfunction "C_K") (pintype "passive"))
      (node (ref "TP19") (pin "TP") (pinfunction "PP_TP") (pintype "input"))
      (node (ref "X101") (pin "9") (pinfunction "9_9") (pintype "passive"))
    )
    (net (code "22") (name "Net-(2I-KL)") (class "Default")
      (node (ref "2") (pin "6") (pinfunction "KL_6") (pintype "passive"))
      (node (ref "JP105") (pin "2") (pinfunction "2_2") (pintype "passive"))
      (node (ref "TP21") (pin "TP") (pinfunction "PP_TP") (pintype "input"))
    )
    (net (code "23") (name "Net-(2J-KL)") (class "Default")
      (node (ref "2") (pin "7") (pinfunction "KL_7") (pintype "passive"))
      (node (ref "LED101") (pin "A") (pinfunction "A_A") (pintype "passive"))
      (node (ref "TP22") (pin "TP") (pinfunction "PP_TP") (pintype "input"))
      (node (ref "X101") (pin "8") (pinfunction "8_8") (pintype "passive"))
    )
    (net (code "24") (name "Net-(2K-KL)") (class "Default")
      (node (ref "2") (pin "8") (pinfunction "KL_8") (pintype "passive"))
      (node (ref "D110") (pin "2") (pinfunction "-_2") (pintype "passive"))
      (node (ref "LED106") (pin "K") (pinfunction "C_K") (pintype "passive"))
      (node (ref "TP23") (pin "TP") (pinfunction "PP_TP") (pintype "input"))
      (node (ref "X101") (pin "14") (pinfunction "14_14") (pintype "passive"))
    )
    (net (code "25") (name "Net-(2L-KL)") (class "Default")
      (node (ref "2") (pin "9") (pinfunction "KL_9") (pintype "passive"))
      (node (ref "D107") (pin "1") (pinfunction "+_1") (pintype "passive"))
      (node (ref "D108") (pin "1") (pinfunction "+_1") (pintype "passive"))
      (node (ref "JP102") (pin "1") (pinfunction "1_1") (pintype "passive"))
      (node (ref "JP103") (pin "2") (pinfunction "2_2") (pintype "passive"))
      (node (ref "TP24") (pin "TP") (pinfunction "PP_TP") (pintype "input"))
    )
    (net (code "26") (name "Net-(C103-Pad1)") (class "Default")
      (node (ref "C103") (pin "1") (pinfunction "1_1") (pintype "passive"))
      (node (ref "R108") (pin "1") (pinfunction "1_1") (pintype "passive"))
      (node (ref "R112") (pin "1") (pinfunction "1_1") (pintype "passive"))
    )
    (net (code "27") (name "Net-(C107-Pad1)") (class "Default")
      (node (ref "C107") (pin "1") (pinfunction "1_1") (pintype "passive"))
      (node (ref "R125") (pin "1") (pinfunction "1_1") (pintype "passive"))
      (node (ref "R130") (pin "2") (pinfunction "2_2") (pintype "passive"))
    )
    (net (code "28") (name "Net-(D1--)") (class "Default")
      (node (ref "D1") (pin "2") (pinfunction "-_2") (pintype "passive"))
      (node (ref "R12") (pin "1") (pinfunction "1_1") (pintype "passive"))
      (node (ref "R13") (pin "1") (pinfunction "1_1") (pintype "passive"))
    )
    (net (code "29") (name "Net-(D2-+)") (class "Default")
      (node (ref "D2") (pin "1") (pinfunction "+_1") (pintype "passive"))
      (node (ref "X101") (pin "1") (pinfunction "1_1") (pintype "passive"))
    )
    (net (code "30") (name "Net-(D104-PadC)") (class "Default")
      (node (ref "D104") (pin "C") (pinfunction "C_C") (pintype "passive"))
      (node (ref "R105") (pin "2") (pinfunction "2_2") (pintype "passive"))
      (node (ref "X101") (pin "22") (pinfunction "22_22") (pintype "passive"))
    )
    (net (code "31") (name "Net-(D105--)") (class "Default")
      (node (ref "D105") (pin "2") (pinfunction "-_2") (pintype "passive"))
      (node (ref "Q104") (pin "2") (pinfunction "C_2") (pintype "passive"))
      (node (ref "START") (pin "TP") (pinfunction "PP_TP") (pintype "input"))
      (node (ref "X101") (pin "5") (pinfunction "5_5") (pintype "passive"))
    )
    (net (code "32") (name "Net-(D106-+)") (class "Default")
      (node (ref "D106") (pin "1") (pinfunction "+_1") (pintype "passive"))
      (node (ref "R127") (pin "1") (pinfunction "1_1") (pintype "passive"))
    )
    (net (code "33") (name "Net-(D109-+)") (class "Default")
      (node (ref "D109") (pin "1") (pinfunction "+_1") (pintype "passive"))
      (node (ref "JP102") (pin "2") (pinfunction "2_2") (pintype "passive"))
    )
    (net (code "34") (name "Net-(D110-+)") (class "Default")
      (node (ref "D110") (pin "1") (pinfunction "+_1") (pintype "passive"))
      (node (ref "JP103") (pin "1") (pinfunction "1_1") (pintype "passive"))
    )
    (net (code "35") (name "Net-(D112-+)") (class "Default")
      (node (ref "D112") (pin "1") (pinfunction "+_1") (pintype "passive"))
      (node (ref "R140") (pin "1") (pinfunction "1_1") (pintype "passive"))
    )
    (net (code "36") (name "Net-(D112--)") (class "Default")
      (node (ref "C109") (pin "2") (pinfunction "2_2") (pintype "passive"))
      (node (ref "D112") (pin "2") (pinfunction "-_2") (pintype "passive"))
      (node (ref "D4") (pin "C") (pinfunction "C_C") (pintype "passive"))
      (node (ref "IC110") (pin "2") (pinfunction "TR_2") (pintype "input"))
      (node (ref "IC110") (pin "6") (pinfunction "THR_6") (pintype "input"))
      (node (ref "R141") (pin "1") (pinfunction "1_1") (pintype "passive"))
    )
    (net (code "37") (name "Net-(IC101A-+IN)") (class "Default")
      (node (ref "C101") (pin "1") (pinfunction "1_1") (pintype "passive"))
      (node (ref "IC101") (pin "3") (pinfunction "+IN_3") (pintype "input"))
      (node (ref "R105") (pin "1") (pinfunction "1_1") (pintype "passive"))
    )
    (net (code "38") (name "Net-(IC101A--IN)") (class "Default")
      (node (ref "IC101") (pin "2") (pinfunction "-IN_2") (pintype "input"))
      (node (ref "R107") (pin "2") (pinfunction "2_2") (pintype "passive"))
    )
    (net (code "39") (name "Net-(IC101A-OUT)") (class "Default")
      (node (ref "IC101") (pin "1") (pinfunction "OUT_1") (pintype "output"))
      (node (ref "R108") (pin "2") (pinfunction "2_2") (pintype "passive"))
    )
    (net (code "40") (name "Net-(IC101B-+IN)") (class "Default")
      (node (ref "IC101") (pin "5") (pinfunction "+IN_5") (pintype "input"))
      (node (ref "Q1") (pin "3") (pinfunction "D_3") (pintype "passive"))
      (node (ref "R112") (pin "2") (pinfunction "2_2") (pintype "passive"))
      (node (ref "R117") (pin "2") (pinfunction "2_2") (pintype "passive"))
    )
    (net (code "41") (name "Net-(IC101B--IN)") (class "Default")
      (node (ref "IC101") (pin "6") (pinfunction "-IN_6") (pintype "input"))
      (node (ref "R113") (pin "1") (pinfunction "1_1") (pintype "passive"))
      (node (ref "R114") (pin "2") (pinfunction "2_2") (pintype "passive"))
    )
    (net (code "42") (name "Net-(IC101B-OUT)") (class "Default")
      (node (ref "IC101") (pin "7") (pinfunction "OUT_7") (pintype "output"))
      (node (ref "R115") (pin "2") (pinfunction "2_2") (pintype "passive"))
      (node (ref "R116") (pin "1") (pinfunction "1_1") (pintype "passive"))
      (node (ref "R117") (pin "1") (pinfunction "1_1") (pintype "passive"))
    )
    (net (code "43") (name "Net-(IC105A-A)") (class "Default")
      (node (ref "IC105") (pin "10") (pinfunction "A_10") (pintype "input"))
      (node (ref "R111") (pin "1") (pinfunction "1_1") (pintype "passive"))
      (node (ref "R3") (pin "1") (pinfunction "1_1") (pintype "passive"))
      (node (ref "R3") (pin "2") (pinfunction "2_2") (pintype "passive"))
      (node (ref "X101") (pin "4") (pinfunction "4_4") (pintype "passive"))
      (node (ref "X103") (pin "2") (pinfunction "S_2") (pintype "passive"))
    )
    (net (code "44") (name "Net-(IC105A-B)") (class "Default")
      (node (ref "IC105") (pin "13") (pinfunction "B_13") (pintype "input"))
      (node (ref "R110") (pin "1") (pinfunction "1_1") (pintype "passive"))
      (node (ref "R2") (pin "1") (pinfunction "1_1") (pintype "passive"))
      (node (ref "R2") (pin "2") (pinfunction "2_2") (pintype "passive"))
      (node (ref "X101") (pin "3") (pinfunction "3_3") (pintype "passive"))
      (node (ref "X103") (pin "3") (pinfunction "S_3") (pintype "passive"))
    )
    (net (code "45") (name "Net-(IC105A-C)") (class "Default")
      (node (ref "IC105") (pin "12") (pinfunction "C_12") (pintype "input"))
      (node (ref "R1") (pin "1") (pinfunction "1_1") (pintype "passive"))
      (node (ref "R1") (pin "2") (pinfunction "2_2") (pintype "passive"))
      (node (ref "R109") (pin "1") (pinfunction "1_1") (pintype "passive"))
      (node (ref "X101") (pin "2") (pinfunction "2_2") (pintype "passive"))
      (node (ref "X103") (pin "4") (pinfunction "S_4") (pintype "passive"))
    )
    (net (code "46") (name "Net-(IC105A-Q0)") (class "Default")
      (node (ref "IC105") (pin "3") (pinfunction "Q0_3") (pintype "output"))
      (node (ref "IC107") (pin "1") (pinfunction "I1_1") (pintype "input"))
      (node (ref "IC107") (pin "2") (pinfunction "I2_2") (pintype "input"))
      (node (ref "Q1") (pin "1") (pinfunction "G_1") (pintype "passive"))
      (node (ref "Q106") (pin "1") (pinfunction "G_1") (pintype "passive"))
    )
    (net (code "47") (name "Net-(IC105A-Q1)") (class "Default")
      (node (ref "IC105") (pin "14") (pinfunction "Q1_14") (pintype "output"))
      (node (ref "IC107") (pin "6") (pinfunction "I6_6") (pintype "input"))
    )
    (net (code "48") (name "Net-(IC105A-Q2)") (class "Default")
      (node (ref "IC105") (pin "2") (pinfunction "Q2_2") (pintype "output"))
      (node (ref "IC107") (pin "7") (pinfunction "I7_7") (pintype "input"))
    )
    (net (code "49") (name "Net-(IC105A-Q3)") (class "Default")
      (node (ref "IC105") (pin "15") (pinfunction "Q3_15") (pintype "output"))
      (node (ref "IC107") (pin "5") (pinfunction "I5_5") (pintype "input"))
    )
    (net (code "50") (name "Net-(IC105A-Q4)") (class "Default")
      (node (ref "IC105") (pin "1") (pinfunction "Q4_1") (pintype "output"))
      (node (ref "IC107") (pin "4") (pinfunction "I4_4") (pintype "input"))
    )
    (net (code "51") (name "Net-(IC105A-Q5)") (class "Default")
      (node (ref "IC105") (pin "6") (pinfunction "Q5_6") (pintype "output"))
      (node (ref "IC107") (pin "3") (pinfunction "I3_3") (pintype "input"))
    )
    (net (code "52") (name "Net-(IC107-O1)") (class "Default")
      (node (ref "IC107") (pin "16") (pinfunction "O1_16") (pintype "open_collector"))
      (node (ref "Q106") (pin "3") (pinfunction "D_3") (pintype "passive"))
      (node (ref "R9") (pin "1") (pinfunction "1_1") (pintype "passive"))
    )
    (net (code "53") (name "Net-(IC107-O2)") (class "Default")
      (node (ref "IC107") (pin "15") (pinfunction "O2_15") (pintype "open_collector"))
      (node (ref "R128") (pin "1") (pinfunction "1_1") (pintype "passive"))
    )
    (net (code "54") (name "Net-(IC108A-+IN)") (class "Default")
      (node (ref "IC108") (pin "11") (pinfunction "+IN_11") (pintype "input"))
      (node (ref "IC108") (pin "5") (pinfunction "+IN_5") (pintype "input"))
      (node (ref "R131") (pin "1") (pinfunction "1_1") (pintype "passive"))
      (node (ref "R132") (pin "2") (pinfunction "2_2") (pintype "passive"))
      (node (ref "R133") (pin "2") (pinfunction "2_2") (pintype "passive"))
    )
    (net (code "55") (name "Net-(IC108A--IN)") (class "Default")
      (node (ref "C108") (pin "1") (pinfunction "1_1") (pintype "passive"))
      (node (ref "IC108") (pin "10") (pinfunction "-IN_10") (pintype "input"))
      (node (ref "IC108") (pin "4") (pinfunction "-IN_4") (pintype "input"))
      (node (ref "R130") (pin "1") (pinfunction "1_1") (pintype "passive"))
    )
    (net (code "56") (name "Net-(IC108A-OUT)") (class "Default")
      (node (ref "IC108") (pin "2") (pinfunction "OUT_2") (pintype "open_collector"))
      (node (ref "R133") (pin "1") (pinfunction "1_1") (pintype "passive"))
    )
    (net (code "57") (name "Net-(IC108B-+IN)") (class "Default")
      (node (ref "IC108") (pin "7") (pinfunction "+IN_7") (pintype "input"))
      (node (ref "R121") (pin "1") (pinfunction "1_1") (pintype "passive"))
      (node (ref "R122") (pin "1") (pinfunction "1_1") (pintype "passive"))
    )
    (net (code "58") (name "Net-(IC108B--IN)") (class "Default")
      (node (ref "IC108") (pin "6") (pinfunction "-IN_6") (pintype "input"))
      (node (ref "IC108") (pin "8") (pinfunction "-IN_8") (pintype "input"))
      (node (ref "R120") (pin "1") (pinfunction "1_1") (pintype "passive"))
    )
    (net (code "59") (name "Net-(IC108B-OUT)") (class "Default")
      (node (ref "IC108") (pin "1") (pinfunction "OUT_1") (pintype "open_collector"))
      (node (ref "R124") (pin "2") (pinfunction "2_2") (pintype "passive"))
      (node (ref "R125") (pin "2") (pinfunction "2_2") (pintype "passive"))
    )
    (net (code "60") (name "Net-(IC108C-+IN)") (class "Default")
      (node (ref "C105") (pin "1") (pinfunction "1_1") (pintype "passive"))
      (node (ref "IC108") (pin "9") (pinfunction "+IN_9") (pintype "input"))
      (node (ref "R122") (pin "2") (pinfunction "2_2") (pintype "passive"))
      (node (ref "R123") (pin "2") (pinfunction "2_2") (pintype "passive"))
    )
    (net (code "61") (name "Net-(IC108C-OUT)") (class "Default")
      (node (ref "C106") (pin "2") (pinfunction "2_2") (pintype "passive"))
      (node (ref "IC108") (pin "14") (pinfunction "OUT_14") (pintype "open_collector"))
      (node (ref "R126") (pin "2") (pinfunction "2_2") (pintype "passive"))
    )
    (net (code "62") (name "Net-(IC108D-OUT)") (class "Default")
      (node (ref "IC108") (pin "13") (pinfunction "OUT_13") (pintype "open_collector"))
      (node (ref "JP105") (pin "1") (pinfunction "1_1") (pintype "passive"))
      (node (ref "Q107") (pin "1") (pinfunction "G_1") (pintype "passive"))
      (node (ref "R135") (pin "2") (pinfunction "2_2") (pintype "passive"))
    )
    (net (code "63") (name "Net-(IC109-ADJ)") (class "Default")
      (node (ref "IC109") (pin "1") (pinfunction "ADJ_1") (pintype "input"))
      (node (ref "R120") (pin "2") (pinfunction "2_2") (pintype "passive"))
      (node (ref "R134") (pin "1") (pinfunction "1_1") (pintype "passive"))
      (node (ref "X101") (pin "7") (pinfunction "7_7") (pintype "passive"))
    )
    (net (code "64") (name "Net-(IC109-VI)") (class "Default")
      (node (ref "IC109") (pin "3") (pinfunction "VI_3") (pintype "input"))
      (node (ref "Q105") (pin "2") (pinfunction "C_2") (pintype "passive"))
    )
    (net (code "65") (name "Net-(IC109-VO)") (class "Default")
      (node (ref "IC109") (pin "2") (pinfunction "VO_2") (pintype "passive"))
      (node (ref "R134") (pin "2") (pinfunction "2_2") (pintype "passive"))
    )
    (net (code "66") (name "Net-(IC110-CV)") (class "Default")
      (node (ref "IC110") (pin "5") (pinfunction "CV_5") (pintype "input"))
      (node (ref "R144") (pin "2") (pinfunction "2_2") (pintype "passive"))
    )
    (net (code "67") (name "Net-(IC110-Q)") (class "Default")
      (node (ref "IC110") (pin "3") (pinfunction "Q_3") (pintype "output"))
      (node (ref "IC111") (pin "12") (pinfunction "A_12") (pintype "input"))
      (node (ref "IC111") (pin "4") (pinfunction "A_4") (pintype "input"))
      (node (ref "R144") (pin "1") (pinfunction "1_1") (pintype "passive"))
    )
    (net (code "68") (name "Net-(IC111A-T2)") (class "Default")
      (node (ref "C15") (pin "2") (pinfunction "2_2") (pintype "passive"))
      (node (ref "IC111") (pin "2") (pinfunction "T2_2") (pintype "input"))
      (node (ref "R10") (pin "1") (pinfunction "1_1") (pintype "passive"))
    )
    (net (code "69") (name "Net-(IC111A-~{Q})") (class "Default")
      (node (ref "IC111") (pin "7") (pinfunction "~{Q}_7") (pintype "output"))
      (node (ref "Q3") (pin "1") (pinfunction "G_1") (pintype "passive"))
    )
    (net (code "70") (name "Net-(IC111B-B)") (class "Default")
      (node (ref "IC111") (pin "11") (pinfunction "B_11") (pintype "input"))
      (node (ref "IC111") (pin "9") (pinfunction "~{Q}_9") (pintype "output"))
      (node (ref "R146") (pin "2") (pinfunction "2_2") (pintype "passive"))
    )
    (net (code "71") (name "Net-(IC111B-T2)") (class "Default")
      (node (ref "C110") (pin "1") (pinfunction "1_1") (pintype "passive"))
      (node (ref "IC111") (pin "14") (pinfunction "T2_14") (pintype "input"))
      (node (ref "R145") (pin "1") (pinfunction "1_1") (pintype "passive"))
    )
    (net (code "72") (name "Net-(JP101-Pad1)") (class "Default")
      (node (ref "JP101") (pin "1") (pinfunction "1_1") (pintype "passive"))
      (node (ref "R119") (pin "2") (pinfunction "2_2") (pintype "passive"))
    )
    (net (code "73") (name "Net-(JP104-Pad2)") (class "Default")
      (node (ref "JP104") (pin "2") (pinfunction "2_2") (pintype "passive"))
      (node (ref "R136") (pin "2") (pinfunction "2_2") (pintype "passive"))
      (node (ref "R137") (pin "2") (pinfunction "2_2") (pintype "passive"))
      (node (ref "SJ101") (pin "2") (pinfunction "2_2") (pintype "passive"))
    )
    (net (code "74") (name "Net-(JP105-Pad3)") (class "Default")
      (node (ref "JP105") (pin "3") (pinfunction "3_3") (pintype "passive"))
      (node (ref "R138") (pin "1") (pinfunction "1_1") (pintype "passive"))
    )
    (net (code "75") (name "Net-(LED101-C)") (class "Default")
      (node (ref "LED101") (pin "K") (pinfunction "C_K") (pintype "passive"))
      (node (ref "R143") (pin "1") (pinfunction "1_1") (pintype "passive"))
    )
    (net (code "76") (name "Net-(LED102-PadA)") (class "Default")
      (node (ref "LED102") (pin "A") (pinfunction "A_A") (pintype "passive"))
      (node (ref "LED103") (pin "A") (pinfunction "A_A") (pintype "passive"))
      (node (ref "LED104") (pin "A") (pinfunction "A_A") (pintype "passive"))
      (node (ref "LED105") (pin "A") (pinfunction "A_A") (pintype "passive"))
      (node (ref "LED106") (pin "A") (pinfunction "A_A") (pintype "passive"))
      (node (ref "R142") (pin "1") (pinfunction "1_1") (pintype "passive"))
    )
    (net (code "77") (name "Net-(Q2-B)") (class "Default")
      (node (ref "Q2") (pin "1") (pinfunction "B_1") (pintype "passive"))
      (node (ref "R8") (pin "1") (pinfunction "1_1") (pintype "passive"))
    )
    (net (code "78") (name "Net-(Q2-C)") (class "Default")
      (node (ref "Q2") (pin "2") (pinfunction "C_2") (pintype "passive"))
      (node (ref "R129") (pin "2") (pinfunction "2_2") (pintype "passive"))
      (node (ref "SJ2") (pin "2") (pinfunction "2_2") (pintype "passive"))
    )
    (net (code "79") (name "Net-(Q3-D)") (class "Default")
      (node (ref "Q3") (pin "3") (pinfunction "D_3") (pintype "passive"))
      (node (ref "R8") (pin "2") (pinfunction "2_2") (pintype "passive"))
    )
    (net (code "80") (name "Net-(Q101-B)") (class "Default")
      (node (ref "Q101") (pin "1") (pinfunction "B_1") (pintype "passive"))
      (node (ref "Q102") (pin "1") (pinfunction "B_1") (pintype "passive"))
      (node (ref "Q102") (pin "2") (pinfunction "C_2") (pintype "passive"))
      (node (ref "R101") (pin "1") (pinfunction "1_1") (pintype "passive"))
      (node (ref "R103") (pin "1") (pinfunction "1_1") (pintype "passive"))
      (node (ref "R104") (pin "1") (pinfunction "1_1") (pintype "passive"))
      (node (ref "X102") (pin "2") (pinfunction "S_2") (pintype "passive"))
    )
    (net (code "81") (name "Net-(Q101-E)") (class "Default")
      (node (ref "Q101") (pin "3") (pinfunction "E_3") (pintype "passive"))
      (node (ref "R102") (pin "2") (pinfunction "2_2") (pintype "passive"))
    )
    (net (code "82") (name "Net-(Q102-E)") (class "Default")
      (node (ref "Q102") (pin "3") (pinfunction "E_3") (pintype "passive"))
      (node (ref "R106") (pin "2") (pinfunction "2_2") (pintype "passive"))
    )
    (net (code "83") (name "Net-(Q103-B)") (class "Default")
      (node (ref "Q103") (pin "1") (pinfunction "B_1") (pintype "passive"))
      (node (ref "R116") (pin "2") (pinfunction "2_2") (pintype "passive"))
      (node (ref "R6") (pin "1") (pinfunction "1_1") (pintype "passive"))
    )
    (net (code "84") (name "Net-(Q103-E)") (class "Default")
      (node (ref "Q103") (pin "3") (pinfunction "E_3") (pintype "passive"))
      (node (ref "R5") (pin "1") (pinfunction "1_1") (pintype "passive"))
    )
    (net (code "85") (name "Net-(Q104-B)") (class "Default")
      (node (ref "Q104") (pin "1") (pinfunction "B_1") (pintype "passive"))
      (node (ref "R128") (pin "2") (pinfunction "2_2") (pintype "passive"))
    )
    (net (code "86") (name "Net-(Q105-B)") (class "Default")
      (node (ref "Q105") (pin "1") (pinfunction "B_1") (pintype "passive"))
      (node (ref "R126") (pin "1") (pinfunction "1_1") (pintype "passive"))
    )
    (net (code "87") (name "Net-(Q106-S)") (class "Default")
      (node (ref "Q106") (pin "2") (pinfunction "S_2") (pintype "passive"))
      (node (ref "R4") (pin "2") (pinfunction "2_2") (pintype "passive"))
    )
    (net (code "88") (name "Net-(Q107-D)") (class "Default")
      (node (ref "Q107") (pin "3") (pinfunction "D_3") (pintype "passive"))
      (node (ref "R138") (pin "2") (pinfunction "2_2") (pintype "passive"))
    )
    (net (code "89") (name "Net-(R115-Pad1)") (class "Default")
      (node (ref "R115") (pin "1") (pinfunction "1_1") (pintype "passive"))
      (node (ref "X101") (pin "21") (pinfunction "21_21") (pintype "passive"))
    )
    (net (code "90") (name "Net-(R127-Pad2)") (class "Default")
      (node (ref "R127") (pin "2") (pinfunction "2_2") (pintype "passive"))
      (node (ref "R129") (pin "1") (pinfunction "1_1") (pintype "passive"))
    )
    (net (code "91") (name "Net-(R140-Pad2)") (class "Default")
      (node (ref "R140") (pin "2") (pinfunction "2_2") (pintype "passive"))
      (node (ref "X101") (pin "16") (pinfunction "16_16") (pintype "passive"))
    )
    (net (code "92") (name "V+") (class "Default")
      (node (ref "D1") (pin "1") (pinfunction "+_1") (pintype "passive"))
      (node (ref "Q104") (pin "3") (pinfunction "E_3") (pintype "passive"))
      (node (ref "Q105") (pin "3") (pinfunction "E_3") (pintype "passive"))
      (node (ref "Q2") (pin "3") (pinfunction "E_3") (pintype "passive"))
      (node (ref "SJ2") (pin "1") (pinfunction "1_1") (pintype "passive"))
      (node (ref "X101") (pin "6") (pinfunction "6_6") (pintype "passive"))
    )
    (net (code "93") (name "VCC") (class "Default")
      (node (ref "6V") (pin "TP") (pinfunction "PP_TP") (pintype "input"))
      (node (ref "C104") (pin "1") (pinfunction "1_1") (pintype "passive"))
      (node (ref "IC101") (pin "8") (pinfunction "V+_8") (pintype "power_in"))
      (node (ref "IC102") (pin "1") (pinfunction "OUT_1") (pintype "passive"))
      (node (ref "IC108") (pin "3") (pinfunction "V+_3") (pintype "power_in"))
      (node (ref "R113") (pin "2") (pinfunction "2_2") (pintype "passive"))
      (node (ref "R121") (pin "2") (pinfunction "2_2") (pintype "passive"))
      (node (ref "R124") (pin "1") (pinfunction "1_1") (pintype "passive"))
      (node (ref "R131") (pin "2") (pinfunction "2_2") (pintype "passive"))
      (node (ref "R142") (pin "2") (pinfunction "2_2") (pintype "passive"))
    )
    (net (code "94") (name "unconnected-(IC105A-Q6-Pad7)") (class "Default")
      (node (ref "IC105") (pin "7") (pinfunction "Q6_7") (pintype "output"))
    )
    (net (code "95") (name "unconnected-(IC105A-Q7-Pad4)") (class "Default")
      (node (ref "IC105") (pin "4") (pinfunction "Q7_4") (pintype "output"))
    )
    (net (code "96") (name "unconnected-(IC105A-Q8-Pad9)") (class "Default")
      (node (ref "IC105") (pin "9") (pinfunction "Q8_9") (pintype "output"))
    )
    (net (code "97") (name "unconnected-(IC105A-Q9-Pad5)") (class "Default")
      (node (ref "IC105") (pin "5") (pinfunction "Q9_5") (pintype "output"))
    )
    (net (code "98") (name "unconnected-(IC110-DIS-Pad7)") (class "Default")
      (node (ref "IC110") (pin "7") (pinfunction "DIS_7") (pintype "input"))
    )
    (net (code "99") (name "unconnected-(IC111A-Q-Pad6)") (class "Default")
      (node (ref "IC111") (pin "6") (pinfunction "Q_6") (pintype "output"))
    )
    (net (code "100") (name "unconnected-(IC111B-Q-Pad10)") (class "Default")
      (node (ref "IC111") (pin "10") (pinfunction "Q_10") (pintype "output"))
    )
    (net (code "101") (name "unconnected-(X101-Pad20)") (class "Default")
      (node (ref "X101") (pin "20") (pinfunction "20_20") (pintype "passive"))
    )
    (net (code "102") (name "unconnected-(X101-Pad24)") (class "Default")
      (node (ref "X101") (pin "24") (pinfunction "24_24") (pintype "passive"))
    )
  )
)
